# MCU.net
KiCad netlist of a schematic drawn in Altium Designer
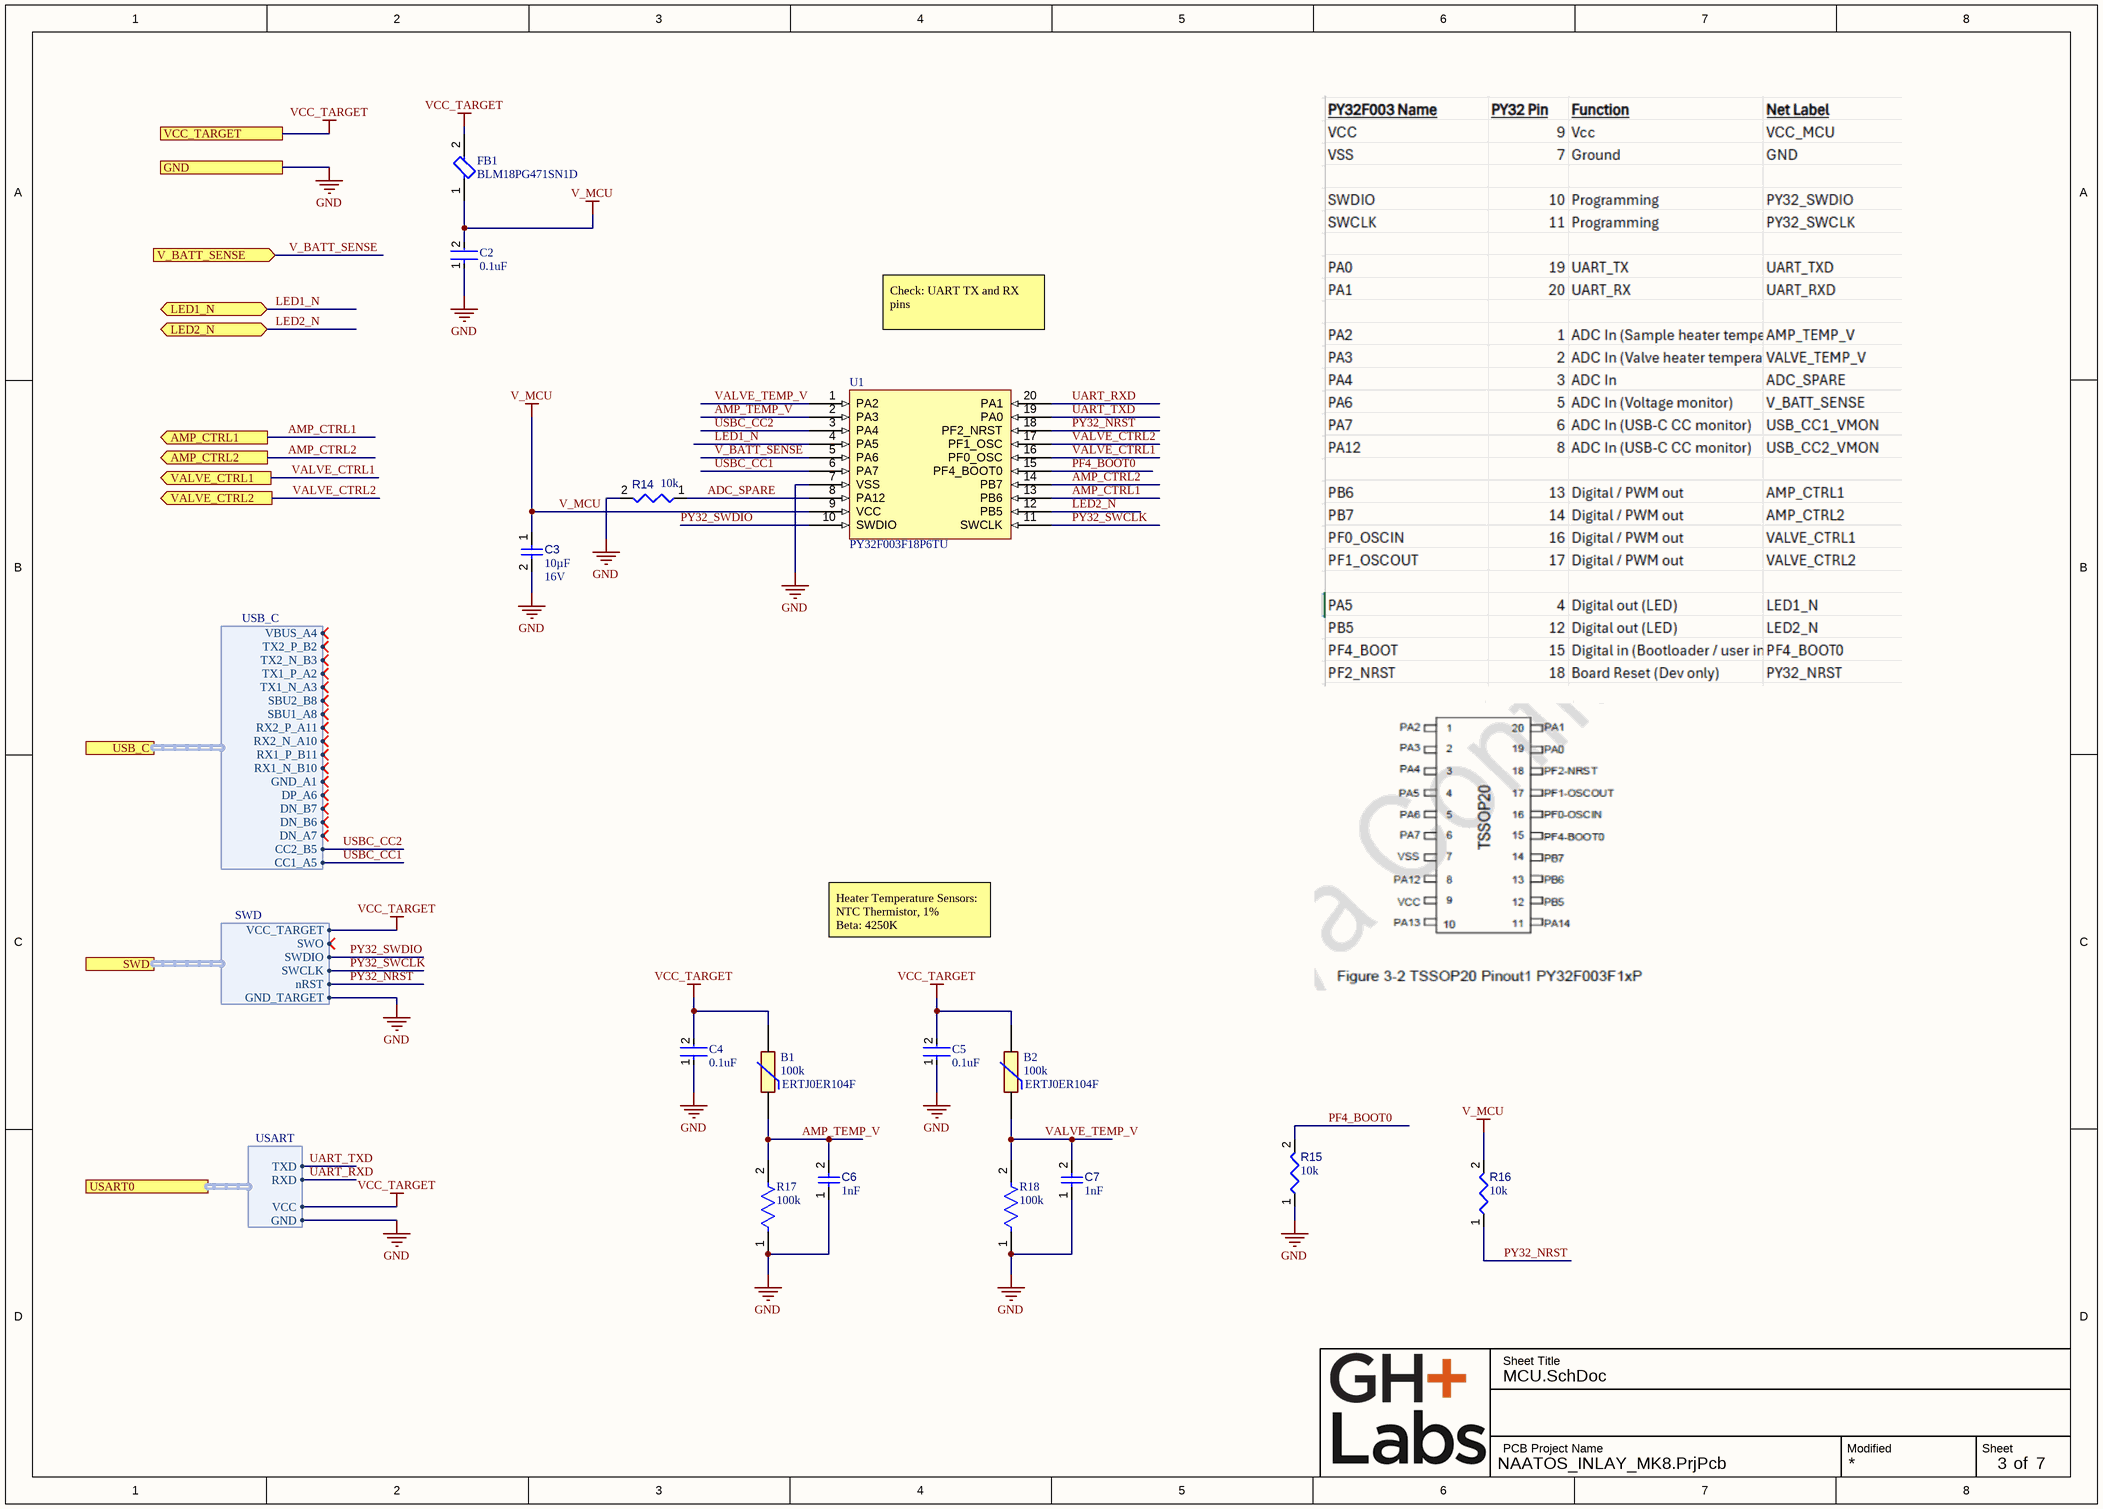
[diagram p0: MCU.SchDoc]

(export (version "E")
  (design (tool "Eeschema 10.0.6"))
  (components
    (comp (ref "B1")
      (value "100k")
      (footprint "THRMC1005X55N")
      (description "Thermistor, NTC, 100k, 1%,  4250k, 0402")
      (fields
        (field (name "POWER") "66mW")
        (field (name "DESIGN ITEM ID") "ERTJ0ER104F")
        (field (name "MOUSER PART NUMBER") "667-ERT-J0ER104FM")
      )
      (libsource (lib "Global Health Labs, Inc") (part "NCP15WF104F03RC"))
    )
    (comp (ref "B2")
      (value "100k")
      (footprint "THRMC1005X55N")
      (description "Thermistor, NTC, 100k, 1%,  4250k, 0402")
      (fields
        (field (name "POWER") "66mW")
        (field (name "DESIGN ITEM ID") "ERTJ0ER104F")
        (field (name "MOUSER PART NUMBER") "667-ERT-J0ER104FM")
      )
      (libsource (lib "Global Health Labs, Inc") (part "NCP15WF104F03RC"))
    )
    (comp (ref "C2")
      (value "0.1uF")
      (footprint "FP-CL17-IPC_C")
      (description "Cap Ceramic 100nF 10V X7R ±10% SMD 0402 +125°C Paper T/R")
      (fields (field (name "TOLERANCE") "10%"))
      (libsource (lib "Altium Content Vault") (part "b4654b650e69147ec39a6b967a45e02"))
    )
    (comp (ref "C3")
      (value "10µF")
      (footprint "CAPC1608X09N")
      (fields (field (name "VOLTAGE RATING") "16V") (field (name "Comment") "CL10A106MO8NQNC"))
      (libsource (lib "Global Health Labs, Inc") (part "CAP-NP-2"))
    )
    (comp (ref "C4")
      (value "0.1uF")
      (footprint "FP-CL17-IPC_C")
      (description "Cap Ceramic 100nF 10V X7R ±10% SMD 0402 +125°C Paper T/R")
      (fields (field (name "TOLERANCE") "10%"))
      (libsource (lib "Altium Content Vault") (part "b4654b650e69147ec39a6b967a45e02"))
    )
    (comp (ref "C5")
      (value "0.1uF")
      (footprint "FP-CL17-IPC_C")
      (description "Cap Ceramic 100nF 10V X7R ±10% SMD 0402 +125°C Paper T/R")
      (fields (field (name "TOLERANCE") "10%"))
      (libsource (lib "Altium Content Vault") (part "b4654b650e69147ec39a6b967a45e02"))
    )
    (comp (ref "C6")
      (value "1nF")
      (footprint "FP-C0402C102K4RAC7411-IPC_B")
      (fields (field (name "Comment") "C0402C102K4RAC7411"))
      (libsource (lib "Global Health Labs, Inc") (part "CAP-NP-2"))
    )
    (comp (ref "C7")
      (value "1nF")
      (footprint "FP-C0402C102K4RAC7411-IPC_B")
      (fields (field (name "Comment") "C0402C102K4RAC7411"))
      (libsource (lib "Global Health Labs, Inc") (part "CAP-NP-2"))
    )
    (comp (ref "FB1")
      (value "BLM18PG471SN1D")
      (footprint "FP-BLM18-0_15-t0_8-MFG")
      (description "Chip Ferrite Bead, 0603, 470Ω @ 100MHz, 0.2Ω, 25%, 1A")
      (fields (field (name "TOLERANCE") "25%"))
      (libsource (lib "Altium Content Vault") (part "5f30dd21d616792df468990f7003faa"))
    )
    (comp (ref "R14")
      (value "10k")
      (footprint "RESC0402(1005)_L")
      (description "Chip Resistor, 10 kOhms, +/-1 %, 63 mW, -55 to 125 degC, 0402")
      (fields (field (name "POWER") "63mW") (field (name "TOLERANCE") "1%"))
      (libsource (lib "Global Health Labs, Inc") (part "RES-2"))
    )
    (comp (ref "R15")
      (value "10k")
      (footprint "RESC0402(1005)_L")
      (description "Chip Resistor, 10 kOhms, +/-1 %, 63 mW, -55 to 125 degC, 0402")
      (fields (field (name "POWER") "63mW") (field (name "TOLERANCE") "1%"))
      (libsource (lib "Global Health Labs, Inc") (part "RES-2"))
    )
    (comp (ref "R16")
      (value "10k")
      (footprint "RESC0402(1005)_L")
      (description "Chip Resistor, 10 kOhms, +/-1 %, 63 mW, -55 to 125 degC, 0402")
      (fields (field (name "POWER") "63mW") (field (name "TOLERANCE") "1%"))
      (libsource (lib "Global Health Labs, Inc") (part "RES-2"))
    )
    (comp (ref "R17")
      (value "CRCW0402100KFKED")
      (footprint "FP-CRCW0402-e3-IPC_C")
      (description "RES Thick Film, 100kΩ, 1%, 0.063W, 100ppm/°C, 0402")
      (fields (field (name "RESISTANCE") "100k") (field (name "TOLERANCE") "1%"))
      (libsource (lib "Altium Content Vault") (part "1029c3af85768c4190bb7ad29bc67b5"))
    )
    (comp (ref "R18")
      (value "CRCW0402100KFKED")
      (footprint "FP-CRCW0402-e3-IPC_C")
      (description "RES Thick Film, 100kΩ, 1%, 0.063W, 100ppm/°C, 0402")
      (fields (field (name "RESISTANCE") "100k") (field (name "TOLERANCE") "1%"))
      (libsource (lib "Altium Content Vault") (part "1029c3af85768c4190bb7ad29bc67b5"))
    )
    (comp (ref "U1")
      (value "PY32F003F18P6TU")
      (footprint "SOP65P640X120-20N")
      (description "IC, MCU, ARM Cortex M0+, TSSOP-20, PY32F003F18P6TU")
      (libsource (lib "Global Health Labs, Inc") (part "PY32F003F18P6TU-Symbol-1"))
    )
  )
  (nets
    (net (code "4") (name "/ADC_SPARE") (class "Default")
      (node (ref "R14") (pin "1") (pinfunction "1_1") (pintype "passive"))
      (node (ref "U1") (pin "8") (pinfunction "PA12_8") (pintype "input"))
    )
    (net (code "5") (name "/AMP_CTRL1") (class "Default")
      (node (ref "U1") (pin "13") (pinfunction "PB6_13") (pintype "input"))
    )
    (net (code "6") (name "/AMP_CTRL2") (class "Default")
      (node (ref "U1") (pin "14") (pinfunction "PB7_14") (pintype "input"))
    )
    (net (code "7") (name "/AMP_TEMP_V") (class "Default")
      (node (ref "B1") (pin "1") (pinfunction "1_1") (pintype "passive"))
      (node (ref "C6") (pin "2") (pinfunction "2_2") (pintype "passive"))
      (node (ref "R17") (pin "2") (pinfunction "2_2") (pintype "passive"))
      (node (ref "U1") (pin "2") (pinfunction "PA3_2") (pintype "input"))
    )
    (net (code "8") (name "/LED1_N") (class "Default")
      (node (ref "U1") (pin "4") (pinfunction "PA5_4") (pintype "input"))
    )
    (net (code "9") (name "/LED2_N") (class "Default")
      (node (ref "U1") (pin "12") (pinfunction "PB5_12") (pintype "input"))
    )
    (net (code "10") (name "/PF4_BOOT0") (class "Default")
      (node (ref "R15") (pin "2") (pinfunction "2_2") (pintype "passive"))
      (node (ref "U1") (pin "15") (pinfunction "PF4_BOOT0_15") (pintype "input"))
    )
    (net (code "11") (name "/PY32_NRST") (class "Default")
      (node (ref "R16") (pin "1") (pinfunction "1_1") (pintype "passive"))
      (node (ref "U1") (pin "18") (pinfunction "PF2_NRST_18") (pintype "input"))
    )
    (net (code "12") (name "/PY32_SWCLK") (class "Default")
      (node (ref "U1") (pin "11") (pinfunction "SWCLK_11") (pintype "input"))
    )
    (net (code "13") (name "/PY32_SWDIO") (class "Default")
      (node (ref "U1") (pin "10") (pinfunction "SWDIO_10") (pintype "input"))
    )
    (net (code "14") (name "/UART_RXD") (class "Default")
      (node (ref "U1") (pin "20") (pinfunction "PA1_20") (pintype "input"))
    )
    (net (code "15") (name "/UART_TXD") (class "Default")
      (node (ref "U1") (pin "19") (pinfunction "PA0_19") (pintype "input"))
    )
    (net (code "16") (name "/USBC_CC1") (class "Default")
      (node (ref "U1") (pin "6") (pinfunction "PA7_6") (pintype "input"))
    )
    (net (code "17") (name "/USBC_CC2") (class "Default")
      (node (ref "U1") (pin "3") (pinfunction "PA4_3") (pintype "input"))
    )
    (net (code "18") (name "/VALVE_CTRL1") (class "Default")
      (node (ref "U1") (pin "16") (pinfunction "PF0_OSC_16") (pintype "input"))
    )
    (net (code "19") (name "/VALVE_CTRL2") (class "Default")
      (node (ref "U1") (pin "17") (pinfunction "PF1_OSC_17") (pintype "input"))
    )
    (net (code "20") (name "/VALVE_TEMP_V") (class "Default")
      (node (ref "B2") (pin "1") (pinfunction "1_1") (pintype "passive"))
      (node (ref "C7") (pin "2") (pinfunction "2_2") (pintype "passive"))
      (node (ref "R18") (pin "2") (pinfunction "2_2") (pintype "passive"))
      (node (ref "U1") (pin "1") (pinfunction "PA2_1") (pintype "input"))
    )
    (net (code "21") (name "/V_BATT_SENSE") (class "Default")
      (node (ref "U1") (pin "5") (pinfunction "PA6_5") (pintype "input"))
    )
    (net (code "25") (name "GND") (class "Default")
      (node (ref "C2") (pin "1") (pinfunction "1_1") (pintype "passive"))
      (node (ref "C3") (pin "2") (pinfunction "2_2") (pintype "passive"))
      (node (ref "C4") (pin "1") (pinfunction "1_1") (pintype "passive"))
      (node (ref "C5") (pin "1") (pinfunction "1_1") (pintype "passive"))
      (node (ref "C6") (pin "1") (pinfunction "1_1") (pintype "passive"))
      (node (ref "C7") (pin "1") (pinfunction "1_1") (pintype "passive"))
      (node (ref "R14") (pin "2") (pinfunction "2_2") (pintype "passive"))
      (node (ref "R15") (pin "1") (pinfunction "1_1") (pintype "passive"))
      (node (ref "R17") (pin "1") (pinfunction "1_1") (pintype "passive"))
      (node (ref "R18") (pin "1") (pinfunction "1_1") (pintype "passive"))
      (node (ref "U1") (pin "7") (pinfunction "VSS_7") (pintype "input"))
    )
    (net (code "26") (name "VCC_TARGET") (class "Default")
      (node (ref "B1") (pin "2") (pinfunction "2_2") (pintype "passive"))
      (node (ref "B2") (pin "2") (pinfunction "2_2") (pintype "passive"))
      (node (ref "C4") (pin "2") (pinfunction "2_2") (pintype "passive"))
      (node (ref "C5") (pin "2") (pinfunction "2_2") (pintype "passive"))
      (node (ref "FB1") (pin "2") (pinfunction "2_2") (pintype "passive"))
    )
    (net (code "27") (name "V_MCU") (class "Default")
      (node (ref "C2") (pin "2") (pinfunction "2_2") (pintype "passive"))
      (node (ref "C3") (pin "1") (pinfunction "1_1") (pintype "passive"))
      (node (ref "FB1") (pin "1") (pinfunction "1_1") (pintype "passive"))
      (node (ref "R16") (pin "2") (pinfunction "2_2") (pintype "passive"))
      (node (ref "U1") (pin "9") (pinfunction "VCC_9") (pintype "input"))
    )
  )
)
